# DipSeq_board_12HP_20150414.net
KiCad netlist of a schematic drawn in EAGLE
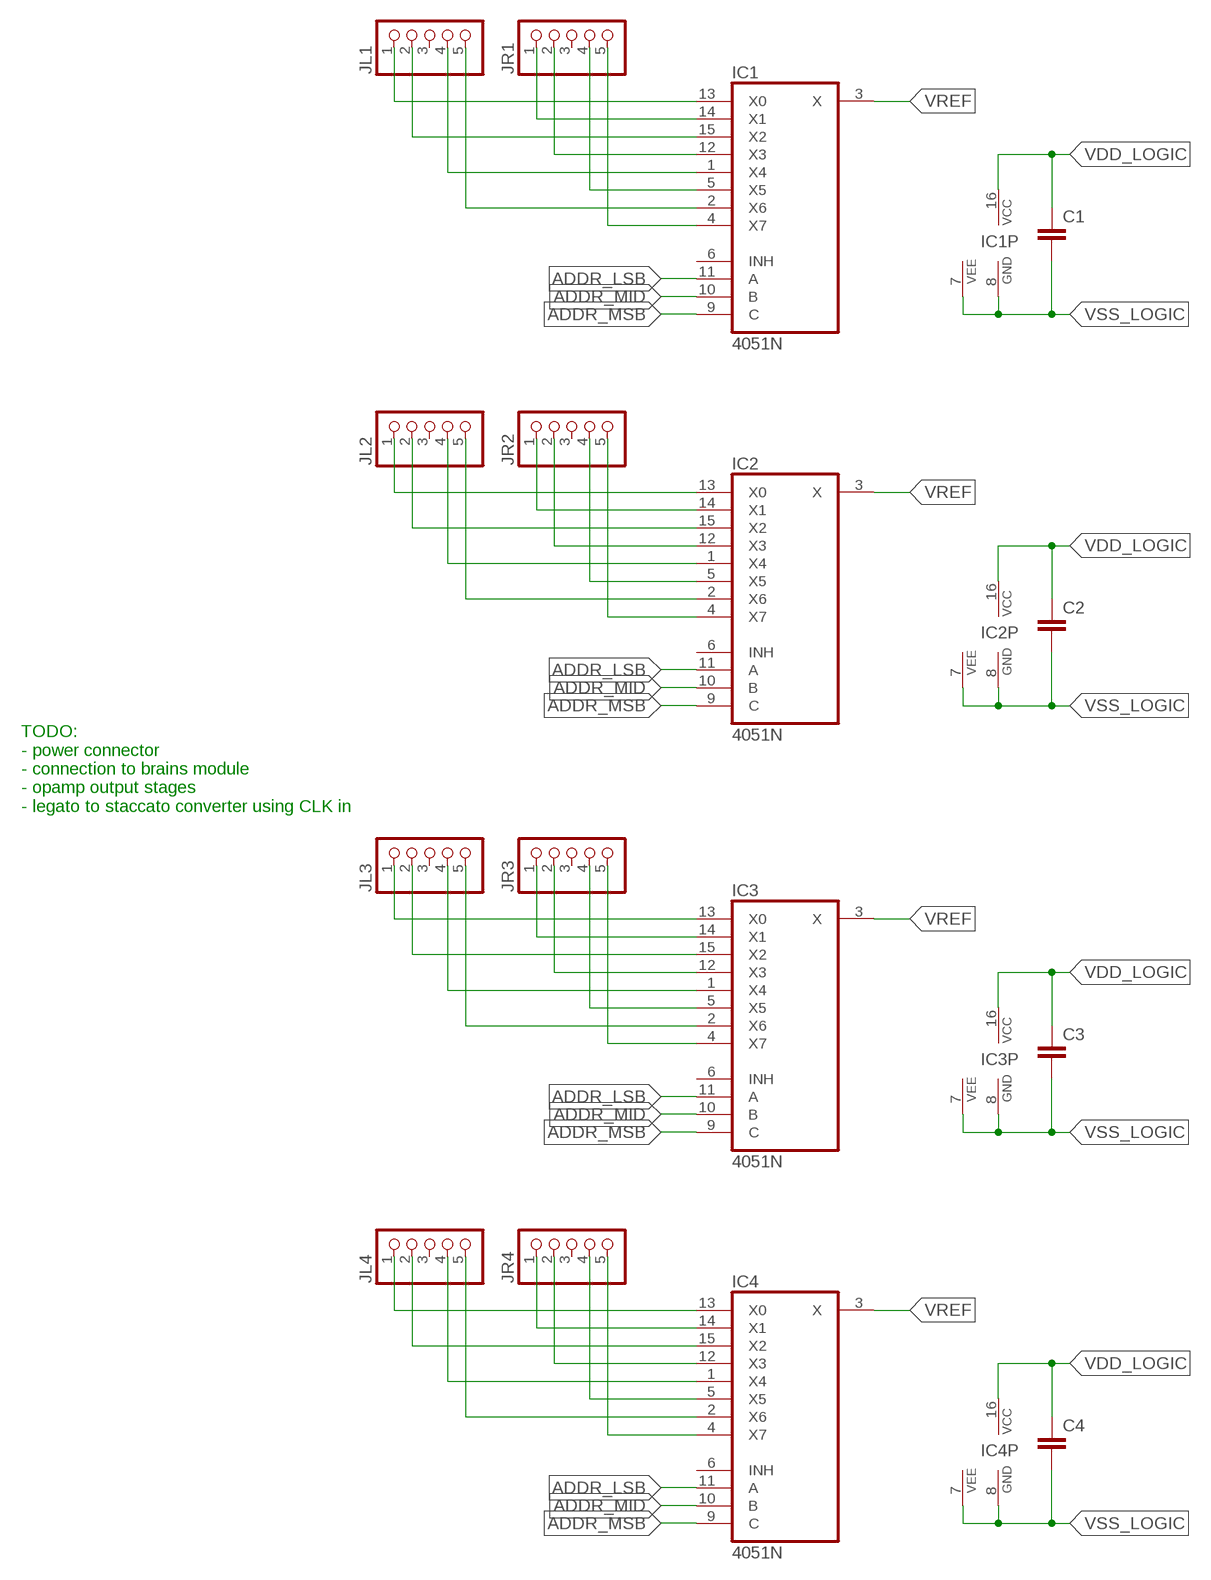
[diagram p0: schematic, sheet 1]
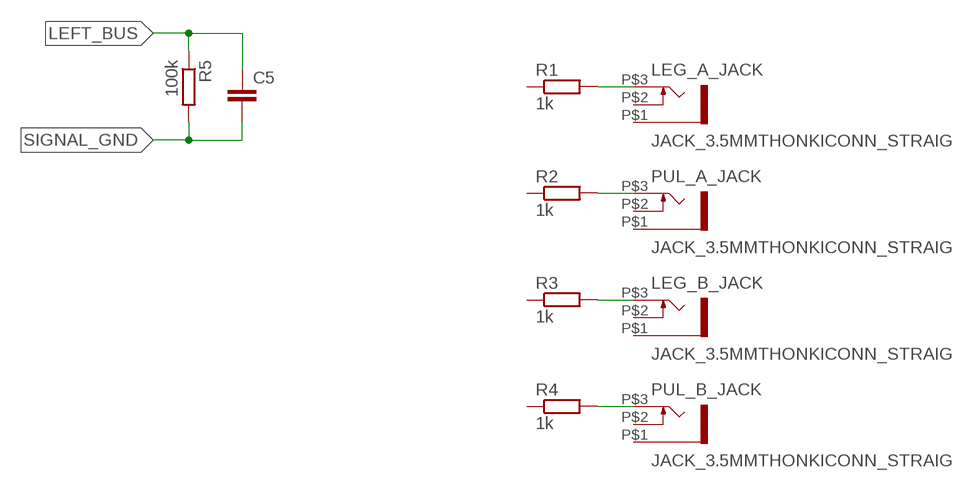
[diagram p1: schematic, sheet 2]
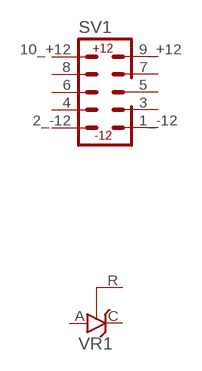
[diagram p2: schematic, sheet 3]

(export (version "E")
  (design (tool "Eeschema 10.0.6"))
  (components
    (comp (ref "SV1")
      (value "BOXHEADER_10P")
      (footprint "eagle-import:MY_BOXHEADER_2X5")
      (libsource (lib "eagle-import") (part "BOXHEADER_10P"))
    )
    (comp (ref "VR1")
      (value "TL431CLP")
      (footprint "eagle-import:TO92-CLP")
      (libsource (lib "eagle-import") (part "TL431CLP"))
    )
    (comp (ref "C1")
      (value "C-EU")
      (footprint "eagle-import:CAP_0805")
      (libsource (lib "eagle-import") (part "C-EU"))
    )
    (comp (ref "C2")
      (value "C-EU")
      (footprint "eagle-import:CAP_0805")
      (libsource (lib "eagle-import") (part "C-EU"))
    )
    (comp (ref "C3")
      (value "C-EU")
      (footprint "eagle-import:CAP_0805")
      (libsource (lib "eagle-import") (part "C-EU"))
    )
    (comp (ref "C4")
      (value "C-EU")
      (footprint "eagle-import:CAP_0805")
      (libsource (lib "eagle-import") (part "C-EU"))
    )
    (comp (ref "IC1")
      (value "4051N")
      (footprint "eagle-import:DIL16")
      (libsource (lib "eagle-import") (part "4051N"))
    )
    (comp (ref "IC2")
      (value "4051N")
      (footprint "eagle-import:DIL16")
      (libsource (lib "eagle-import") (part "4051N"))
    )
    (comp (ref "IC3")
      (value "4051N")
      (footprint "eagle-import:DIL16")
      (libsource (lib "eagle-import") (part "4051N"))
    )
    (comp (ref "IC4")
      (value "4051N")
      (footprint "eagle-import:DIL16")
      (libsource (lib "eagle-import") (part "4051N"))
    )
    (comp (ref "JL1")
      (value "PINHD-1X5")
      (footprint "eagle-import:1X05")
      (libsource (lib "eagle-import") (part "PINHD-1X5"))
    )
    (comp (ref "JL2")
      (value "PINHD-1X5")
      (footprint "eagle-import:1X05")
      (libsource (lib "eagle-import") (part "PINHD-1X5"))
    )
    (comp (ref "JL3")
      (value "PINHD-1X5")
      (footprint "eagle-import:1X05")
      (libsource (lib "eagle-import") (part "PINHD-1X5"))
    )
    (comp (ref "JL4")
      (value "PINHD-1X5")
      (footprint "eagle-import:1X05")
      (libsource (lib "eagle-import") (part "PINHD-1X5"))
    )
    (comp (ref "JR1")
      (value "PINHD-1X5")
      (footprint "eagle-import:1X05")
      (libsource (lib "eagle-import") (part "PINHD-1X5"))
    )
    (comp (ref "JR2")
      (value "PINHD-1X5")
      (footprint "eagle-import:1X05")
      (libsource (lib "eagle-import") (part "PINHD-1X5"))
    )
    (comp (ref "JR3")
      (value "PINHD-1X5")
      (footprint "eagle-import:1X05")
      (libsource (lib "eagle-import") (part "PINHD-1X5"))
    )
    (comp (ref "JR4")
      (value "PINHD-1X5")
      (footprint "eagle-import:1X05")
      (libsource (lib "eagle-import") (part "PINHD-1X5"))
    )
    (comp (ref "C5")
      (value "C-EU")
      (footprint "eagle-import:CAP_0805")
      (libsource (lib "eagle-import") (part "C-EU"))
    )
    (comp (ref "LEG_A_JACK")
      (value "JACK_3.5MMTHONKICONN_STRAIGHT")
      (footprint "eagle-import:THONKICONN_LAYOUT")
      (libsource (lib "eagle-import") (part "JACK_3.5MMTHONKICONN_STRAIGHT"))
    )
    (comp (ref "LEG_B_JACK")
      (value "JACK_3.5MMTHONKICONN_STRAIGHT")
      (footprint "eagle-import:THONKICONN_LAYOUT")
      (libsource (lib "eagle-import") (part "JACK_3.5MMTHONKICONN_STRAIGHT"))
    )
    (comp (ref "PUL_A_JACK")
      (value "JACK_3.5MMTHONKICONN_STRAIGHT")
      (footprint "eagle-import:THONKICONN_LAYOUT")
      (libsource (lib "eagle-import") (part "JACK_3.5MMTHONKICONN_STRAIGHT"))
    )
    (comp (ref "PUL_B_JACK")
      (value "JACK_3.5MMTHONKICONN_STRAIGHT")
      (footprint "eagle-import:THONKICONN_LAYOUT")
      (libsource (lib "eagle-import") (part "JACK_3.5MMTHONKICONN_STRAIGHT"))
    )
    (comp (ref "R1")
      (value "1k")
      (footprint "eagle-import:R_0805_MINE")
      (libsource (lib "eagle-import") (part "R-EU_R0805W"))
    )
    (comp (ref "R2")
      (value "1k")
      (footprint "eagle-import:R_0805_MINE")
      (libsource (lib "eagle-import") (part "R-EU_R0805W"))
    )
    (comp (ref "R3")
      (value "1k")
      (footprint "eagle-import:R_0805_MINE")
      (libsource (lib "eagle-import") (part "R-EU_R0805W"))
    )
    (comp (ref "R4")
      (value "1k")
      (footprint "eagle-import:R_0805_MINE")
      (libsource (lib "eagle-import") (part "R-EU_R0805W"))
    )
    (comp (ref "R5")
      (value "100k")
      (footprint "eagle-import:R_0805_MINE")
      (libsource (lib "eagle-import") (part "R-EU_R0805W"))
    )
  )
  (nets
    (net (code "1") (name "ADDR_LSB") (class "Default")
      (node (ref "IC1") (pin "11") (pinfunction "A_11") (pintype "input"))
      (node (ref "IC2") (pin "11") (pinfunction "A_11") (pintype "input"))
      (node (ref "IC3") (pin "11") (pinfunction "A_11") (pintype "input"))
      (node (ref "IC4") (pin "11") (pinfunction "A_11") (pintype "input"))
    )
    (net (code "2") (name "ADDR_MID") (class "Default")
      (node (ref "IC1") (pin "10") (pinfunction "B_10") (pintype "input"))
      (node (ref "IC2") (pin "10") (pinfunction "B_10") (pintype "input"))
      (node (ref "IC3") (pin "10") (pinfunction "B_10") (pintype "input"))
      (node (ref "IC4") (pin "10") (pinfunction "B_10") (pintype "input"))
    )
    (net (code "3") (name "ADDR_MSB") (class "Default")
      (node (ref "IC1") (pin "9") (pinfunction "C_9") (pintype "input"))
      (node (ref "IC2") (pin "9") (pinfunction "C_9") (pintype "input"))
      (node (ref "IC3") (pin "9") (pinfunction "C_9") (pintype "input"))
      (node (ref "IC4") (pin "9") (pinfunction "C_9") (pintype "input"))
    )
    (net (code "4") (name "LEFT_BUS") (class "Default")
      (node (ref "C5") (pin "1") (pinfunction "1_1") (pintype "passive"))
      (node (ref "R5") (pin "1") (pinfunction "1_1") (pintype "passive"))
    )
    (net (code "5") (name "Net-(IC1A-X0)") (class "Default")
      (node (ref "IC1") (pin "13") (pinfunction "X0_13") (pintype "bidirectional"))
      (node (ref "JL1") (pin "1") (pinfunction "1_1") (pintype "passive"))
    )
    (net (code "6") (name "Net-(IC1A-X1)") (class "Default")
      (node (ref "IC1") (pin "14") (pinfunction "X1_14") (pintype "bidirectional"))
      (node (ref "JR1") (pin "1") (pinfunction "1_1") (pintype "passive"))
    )
    (net (code "7") (name "Net-(IC1A-X2)") (class "Default")
      (node (ref "IC1") (pin "15") (pinfunction "X2_15") (pintype "bidirectional"))
      (node (ref "JL1") (pin "2") (pinfunction "2_2") (pintype "passive"))
    )
    (net (code "8") (name "Net-(IC1A-X3)") (class "Default")
      (node (ref "IC1") (pin "12") (pinfunction "X3_12") (pintype "bidirectional"))
      (node (ref "JR1") (pin "2") (pinfunction "2_2") (pintype "passive"))
    )
    (net (code "9") (name "Net-(IC1A-X4)") (class "Default")
      (node (ref "IC1") (pin "1") (pinfunction "X4_1") (pintype "bidirectional"))
      (node (ref "JL1") (pin "4") (pinfunction "4_4") (pintype "passive"))
    )
    (net (code "10") (name "Net-(IC1A-X5)") (class "Default")
      (node (ref "IC1") (pin "5") (pinfunction "X5_5") (pintype "bidirectional"))
      (node (ref "JR1") (pin "4") (pinfunction "4_4") (pintype "passive"))
    )
    (net (code "11") (name "Net-(IC1A-X6)") (class "Default")
      (node (ref "IC1") (pin "2") (pinfunction "X6_2") (pintype "bidirectional"))
      (node (ref "JL1") (pin "5") (pinfunction "5_5") (pintype "passive"))
    )
    (net (code "12") (name "Net-(IC1A-X7)") (class "Default")
      (node (ref "IC1") (pin "4") (pinfunction "X7_4") (pintype "bidirectional"))
      (node (ref "JR1") (pin "5") (pinfunction "5_5") (pintype "passive"))
    )
    (net (code "13") (name "Net-(IC2A-X0)") (class "Default")
      (node (ref "IC2") (pin "13") (pinfunction "X0_13") (pintype "bidirectional"))
      (node (ref "JL2") (pin "1") (pinfunction "1_1") (pintype "passive"))
    )
    (net (code "14") (name "Net-(IC2A-X1)") (class "Default")
      (node (ref "IC2") (pin "14") (pinfunction "X1_14") (pintype "bidirectional"))
      (node (ref "JR2") (pin "1") (pinfunction "1_1") (pintype "passive"))
    )
    (net (code "15") (name "Net-(IC2A-X2)") (class "Default")
      (node (ref "IC2") (pin "15") (pinfunction "X2_15") (pintype "bidirectional"))
      (node (ref "JL2") (pin "2") (pinfunction "2_2") (pintype "passive"))
    )
    (net (code "16") (name "Net-(IC2A-X3)") (class "Default")
      (node (ref "IC2") (pin "12") (pinfunction "X3_12") (pintype "bidirectional"))
      (node (ref "JR2") (pin "2") (pinfunction "2_2") (pintype "passive"))
    )
    (net (code "17") (name "Net-(IC2A-X4)") (class "Default")
      (node (ref "IC2") (pin "1") (pinfunction "X4_1") (pintype "bidirectional"))
      (node (ref "JL2") (pin "4") (pinfunction "4_4") (pintype "passive"))
    )
    (net (code "18") (name "Net-(IC2A-X5)") (class "Default")
      (node (ref "IC2") (pin "5") (pinfunction "X5_5") (pintype "bidirectional"))
      (node (ref "JR2") (pin "4") (pinfunction "4_4") (pintype "passive"))
    )
    (net (code "19") (name "Net-(IC2A-X6)") (class "Default")
      (node (ref "IC2") (pin "2") (pinfunction "X6_2") (pintype "bidirectional"))
      (node (ref "JL2") (pin "5") (pinfunction "5_5") (pintype "passive"))
    )
    (net (code "20") (name "Net-(IC2A-X7)") (class "Default")
      (node (ref "IC2") (pin "4") (pinfunction "X7_4") (pintype "bidirectional"))
      (node (ref "JR2") (pin "5") (pinfunction "5_5") (pintype "passive"))
    )
    (net (code "21") (name "Net-(IC3A-X0)") (class "Default")
      (node (ref "IC3") (pin "13") (pinfunction "X0_13") (pintype "bidirectional"))
      (node (ref "JL3") (pin "1") (pinfunction "1_1") (pintype "passive"))
    )
    (net (code "22") (name "Net-(IC3A-X1)") (class "Default")
      (node (ref "IC3") (pin "14") (pinfunction "X1_14") (pintype "bidirectional"))
      (node (ref "JR3") (pin "1") (pinfunction "1_1") (pintype "passive"))
    )
    (net (code "23") (name "Net-(IC3A-X2)") (class "Default")
      (node (ref "IC3") (pin "15") (pinfunction "X2_15") (pintype "bidirectional"))
      (node (ref "JL3") (pin "2") (pinfunction "2_2") (pintype "passive"))
    )
    (net (code "24") (name "Net-(IC3A-X3)") (class "Default")
      (node (ref "IC3") (pin "12") (pinfunction "X3_12") (pintype "bidirectional"))
      (node (ref "JR3") (pin "2") (pinfunction "2_2") (pintype "passive"))
    )
    (net (code "25") (name "Net-(IC3A-X4)") (class "Default")
      (node (ref "IC3") (pin "1") (pinfunction "X4_1") (pintype "bidirectional"))
      (node (ref "JL3") (pin "4") (pinfunction "4_4") (pintype "passive"))
    )
    (net (code "26") (name "Net-(IC3A-X5)") (class "Default")
      (node (ref "IC3") (pin "5") (pinfunction "X5_5") (pintype "bidirectional"))
      (node (ref "JR3") (pin "4") (pinfunction "4_4") (pintype "passive"))
    )
    (net (code "27") (name "Net-(IC3A-X6)") (class "Default")
      (node (ref "IC3") (pin "2") (pinfunction "X6_2") (pintype "bidirectional"))
      (node (ref "JL3") (pin "5") (pinfunction "5_5") (pintype "passive"))
    )
    (net (code "28") (name "Net-(IC3A-X7)") (class "Default")
      (node (ref "IC3") (pin "4") (pinfunction "X7_4") (pintype "bidirectional"))
      (node (ref "JR3") (pin "5") (pinfunction "5_5") (pintype "passive"))
    )
    (net (code "29") (name "Net-(IC4A-X0)") (class "Default")
      (node (ref "IC4") (pin "13") (pinfunction "X0_13") (pintype "bidirectional"))
      (node (ref "JL4") (pin "1") (pinfunction "1_1") (pintype "passive"))
    )
    (net (code "30") (name "Net-(IC4A-X1)") (class "Default")
      (node (ref "IC4") (pin "14") (pinfunction "X1_14") (pintype "bidirectional"))
      (node (ref "JR4") (pin "1") (pinfunction "1_1") (pintype "passive"))
    )
    (net (code "31") (name "Net-(IC4A-X2)") (class "Default")
      (node (ref "IC4") (pin "15") (pinfunction "X2_15") (pintype "bidirectional"))
      (node (ref "JL4") (pin "2") (pinfunction "2_2") (pintype "passive"))
    )
    (net (code "32") (name "Net-(IC4A-X3)") (class "Default")
      (node (ref "IC4") (pin "12") (pinfunction "X3_12") (pintype "bidirectional"))
      (node (ref "JR4") (pin "2") (pinfunction "2_2") (pintype "passive"))
    )
    (net (code "33") (name "Net-(IC4A-X4)") (class "Default")
      (node (ref "IC4") (pin "1") (pinfunction "X4_1") (pintype "bidirectional"))
      (node (ref "JL4") (pin "4") (pinfunction "4_4") (pintype "passive"))
    )
    (net (code "34") (name "Net-(IC4A-X5)") (class "Default")
      (node (ref "IC4") (pin "5") (pinfunction "X5_5") (pintype "bidirectional"))
      (node (ref "JR4") (pin "4") (pinfunction "4_4") (pintype "passive"))
    )
    (net (code "35") (name "Net-(IC4A-X6)") (class "Default")
      (node (ref "IC4") (pin "2") (pinfunction "X6_2") (pintype "bidirectional"))
      (node (ref "JL4") (pin "5") (pinfunction "5_5") (pintype "passive"))
    )
    (net (code "36") (name "Net-(IC4A-X7)") (class "Default")
      (node (ref "IC4") (pin "4") (pinfunction "X7_4") (pintype "bidirectional"))
      (node (ref "JR4") (pin "5") (pinfunction "5_5") (pintype "passive"))
    )
    (net (code "37") (name "Net-(LEG_A_JACK-TIP)") (class "Default")
      (node (ref "LEG_A_JACK") (pin "P$3") (pinfunction "TIP_P$3") (pintype "passive"))
      (node (ref "R1") (pin "2") (pinfunction "2_2") (pintype "passive"))
    )
    (net (code "38") (name "Net-(LEG_B_JACK-TIP)") (class "Default")
      (node (ref "LEG_B_JACK") (pin "P$3") (pinfunction "TIP_P$3") (pintype "passive"))
      (node (ref "R3") (pin "2") (pinfunction "2_2") (pintype "passive"))
    )
    (net (code "39") (name "Net-(PUL_A_JACK-TIP)") (class "Default")
      (node (ref "PUL_A_JACK") (pin "P$3") (pinfunction "TIP_P$3") (pintype "passive"))
      (node (ref "R2") (pin "2") (pinfunction "2_2") (pintype "passive"))
    )
    (net (code "40") (name "Net-(PUL_B_JACK-TIP)") (class "Default")
      (node (ref "PUL_B_JACK") (pin "P$3") (pinfunction "TIP_P$3") (pintype "passive"))
      (node (ref "R4") (pin "2") (pinfunction "2_2") (pintype "passive"))
    )
    (net (code "41") (name "SIGNAL_GND") (class "Default")
      (node (ref "C5") (pin "2") (pinfunction "2_2") (pintype "passive"))
      (node (ref "R5") (pin "2") (pinfunction "2_2") (pintype "passive"))
    )
    (net (code "42") (name "VDD_LOGIC") (class "Default")
      (node (ref "C1") (pin "1") (pinfunction "1_1") (pintype "passive"))
      (node (ref "C2") (pin "1") (pinfunction "1_1") (pintype "passive"))
      (node (ref "C3") (pin "1") (pinfunction "1_1") (pintype "passive"))
      (node (ref "C4") (pin "1") (pinfunction "1_1") (pintype "passive"))
      (node (ref "IC1") (pin "16") (pinfunction "VCC_16") (pintype "power_in"))
      (node (ref "IC2") (pin "16") (pinfunction "VCC_16") (pintype "power_in"))
      (node (ref "IC3") (pin "16") (pinfunction "VCC_16") (pintype "power_in"))
      (node (ref "IC4") (pin "16") (pinfunction "VCC_16") (pintype "power_in"))
    )
    (net (code "43") (name "VREF") (class "Default")
      (node (ref "IC1") (pin "3") (pinfunction "X_3") (pintype "bidirectional"))
      (node (ref "IC2") (pin "3") (pinfunction "X_3") (pintype "bidirectional"))
      (node (ref "IC3") (pin "3") (pinfunction "X_3") (pintype "bidirectional"))
      (node (ref "IC4") (pin "3") (pinfunction "X_3") (pintype "bidirectional"))
    )
    (net (code "44") (name "VSS_LOGIC") (class "Default")
      (node (ref "C1") (pin "2") (pinfunction "2_2") (pintype "passive"))
      (node (ref "C2") (pin "2") (pinfunction "2_2") (pintype "passive"))
      (node (ref "C3") (pin "2") (pinfunction "2_2") (pintype "passive"))
      (node (ref "C4") (pin "2") (pinfunction "2_2") (pintype "passive"))
      (node (ref "IC1") (pin "7") (pinfunction "VEE_7") (pintype "power_in"))
      (node (ref "IC1") (pin "8") (pinfunction "GND_8") (pintype "power_in"))
      (node (ref "IC2") (pin "7") (pinfunction "VEE_7") (pintype "power_in"))
      (node (ref "IC2") (pin "8") (pinfunction "GND_8") (pintype "power_in"))
      (node (ref "IC3") (pin "7") (pinfunction "VEE_7") (pintype "power_in"))
      (node (ref "IC3") (pin "8") (pinfunction "GND_8") (pintype "power_in"))
      (node (ref "IC4") (pin "7") (pinfunction "VEE_7") (pintype "power_in"))
      (node (ref "IC4") (pin "8") (pinfunction "GND_8") (pintype "power_in"))
    )
    (net (code "45") (name "unconnected-(IC1A-INH-Pad6)") (class "Default")
      (node (ref "IC1") (pin "6") (pinfunction "INH_6") (pintype "input"))
    )
    (net (code "46") (name "unconnected-(IC2A-INH-Pad6)") (class "Default")
      (node (ref "IC2") (pin "6") (pinfunction "INH_6") (pintype "input"))
    )
    (net (code "47") (name "unconnected-(IC3A-INH-Pad6)") (class "Default")
      (node (ref "IC3") (pin "6") (pinfunction "INH_6") (pintype "input"))
    )
    (net (code "48") (name "unconnected-(IC4A-INH-Pad6)") (class "Default")
      (node (ref "IC4") (pin "6") (pinfunction "INH_6") (pintype "input"))
    )
    (net (code "49") (name "unconnected-(JL1-Pad3)") (class "Default")
      (node (ref "JL1") (pin "3") (pinfunction "3_3") (pintype "passive"))
    )
    (net (code "50") (name "unconnected-(JL2-Pad3)") (class "Default")
      (node (ref "JL2") (pin "3") (pinfunction "3_3") (pintype "passive"))
    )
    (net (code "51") (name "unconnected-(JL3-Pad3)") (class "Default")
      (node (ref "JL3") (pin "3") (pinfunction "3_3") (pintype "passive"))
    )
    (net (code "52") (name "unconnected-(JL4-Pad3)") (class "Default")
      (node (ref "JL4") (pin "3") (pinfunction "3_3") (pintype "passive"))
    )
    (net (code "53") (name "unconnected-(JR1-Pad3)") (class "Default")
      (node (ref "JR1") (pin "3") (pinfunction "3_3") (pintype "passive"))
    )
    (net (code "54") (name "unconnected-(JR2-Pad3)") (class "Default")
      (node (ref "JR2") (pin "3") (pinfunction "3_3") (pintype "passive"))
    )
    (net (code "55") (name "unconnected-(JR3-Pad3)") (class "Default")
      (node (ref "JR3") (pin "3") (pinfunction "3_3") (pintype "passive"))
    )
    (net (code "56") (name "unconnected-(JR4-Pad3)") (class "Default")
      (node (ref "JR4") (pin "3") (pinfunction "3_3") (pintype "passive"))
    )
    (net (code "57") (name "unconnected-(LEG_A_JACK-SLEEVE-PadP$1)") (class "Default")
      (node (ref "LEG_A_JACK") (pin "P$1") (pinfunction "SLEEVE_P$1") (pintype "passive"))
    )
    (net (code "58") (name "unconnected-(LEG_A_JACK-SWITCH-PadP$2)") (class "Default")
      (node (ref "LEG_A_JACK") (pin "P$2") (pinfunction "SWITCH_P$2") (pintype "passive"))
    )
    (net (code "59") (name "unconnected-(LEG_B_JACK-SLEEVE-PadP$1)") (class "Default")
      (node (ref "LEG_B_JACK") (pin "P$1") (pinfunction "SLEEVE_P$1") (pintype "passive"))
    )
    (net (code "60") (name "unconnected-(LEG_B_JACK-SWITCH-PadP$2)") (class "Default")
      (node (ref "LEG_B_JACK") (pin "P$2") (pinfunction "SWITCH_P$2") (pintype "passive"))
    )
    (net (code "61") (name "unconnected-(PUL_A_JACK-SLEEVE-PadP$1)") (class "Default")
      (node (ref "PUL_A_JACK") (pin "P$1") (pinfunction "SLEEVE_P$1") (pintype "passive"))
    )
    (net (code "62") (name "unconnected-(PUL_A_JACK-SWITCH-PadP$2)") (class "Default")
      (node (ref "PUL_A_JACK") (pin "P$2") (pinfunction "SWITCH_P$2") (pintype "passive"))
    )
    (net (code "63") (name "unconnected-(PUL_B_JACK-SLEEVE-PadP$1)") (class "Default")
      (node (ref "PUL_B_JACK") (pin "P$1") (pinfunction "SLEEVE_P$1") (pintype "passive"))
    )
    (net (code "64") (name "unconnected-(PUL_B_JACK-SWITCH-PadP$2)") (class "Default")
      (node (ref "PUL_B_JACK") (pin "P$2") (pinfunction "SWITCH_P$2") (pintype "passive"))
    )
    (net (code "65") (name "unconnected-(R1-Pad1)") (class "Default")
      (node (ref "R1") (pin "1") (pinfunction "1_1") (pintype "passive"))
    )
    (net (code "66") (name "unconnected-(R2-Pad1)") (class "Default")
      (node (ref "R2") (pin "1") (pinfunction "1_1") (pintype "passive"))
    )
    (net (code "67") (name "unconnected-(R3-Pad1)") (class "Default")
      (node (ref "R3") (pin "1") (pinfunction "1_1") (pintype "passive"))
    )
    (net (code "68") (name "unconnected-(R4-Pad1)") (class "Default")
      (node (ref "R4") (pin "1") (pinfunction "1_1") (pintype "passive"))
    )
    (net (code "69") (name "unconnected-(SV1-3_GND-Pad3)") (class "Default")
      (node (ref "SV1") (pin "3") (pinfunction "3_GND_3") (pintype "passive"))
    )
    (net (code "70") (name "unconnected-(SV1-4_GND-Pad4)") (class "Default")
      (node (ref "SV1") (pin "4") (pinfunction "4_GND_4") (pintype "passive"))
    )
    (net (code "71") (name "unconnected-(SV1-5_GND-Pad5)") (class "Default")
      (node (ref "SV1") (pin "5") (pinfunction "5_GND_5") (pintype "passive"))
    )
    (net (code "72") (name "unconnected-(SV1-6_GND-Pad6)") (class "Default")
      (node (ref "SV1") (pin "6") (pinfunction "6_GND_6") (pintype "passive"))
    )
    (net (code "73") (name "unconnected-(SV1-7_GND-Pad7)") (class "Default")
      (node (ref "SV1") (pin "7") (pinfunction "7_GND_7") (pintype "passive"))
    )
    (net (code "74") (name "unconnected-(SV1-8_GND-Pad8)") (class "Default")
      (node (ref "SV1") (pin "8") (pinfunction "8_GND_8") (pintype "passive"))
    )
    (net (code "75") (name "unconnected-(SV1-Pad1_-12)") (class "Default")
      (node (ref "SV1") (pin "1_-12") (pinfunction "1_-12_1_-12") (pintype "passive"))
    )
    (net (code "76") (name "unconnected-(SV1-Pad2_-12)") (class "Default")
      (node (ref "SV1") (pin "2_-12") (pinfunction "2_-12_2_-12") (pintype "passive"))
    )
    (net (code "77") (name "unconnected-(SV1-Pad9_+12)") (class "Default")
      (node (ref "SV1") (pin "9_+12") (pinfunction "9_+12_9_+12") (pintype "passive"))
    )
    (net (code "78") (name "unconnected-(SV1-Pad10_+12)") (class "Default")
      (node (ref "SV1") (pin "10_+12") (pinfunction "10_+12_10_+12") (pintype "passive"))
    )
    (net (code "79") (name "unconnected-(VR1-PadA)") (class "Default")
      (node (ref "VR1") (pin "A") (pinfunction "A_A") (pintype "passive"))
    )
    (net (code "80") (name "unconnected-(VR1-PadC)") (class "Default")
      (node (ref "VR1") (pin "C") (pinfunction "C_C") (pintype "passive"))
    )
    (net (code "81") (name "unconnected-(VR1-PadR)") (class "Default")
      (node (ref "VR1") (pin "R") (pinfunction "R_R") (pintype "passive"))
    )
  )
)
